# ATmega128RFA1-DevBoard-rev2_routed.net
KiCad netlist of a schematic drawn in EAGLE
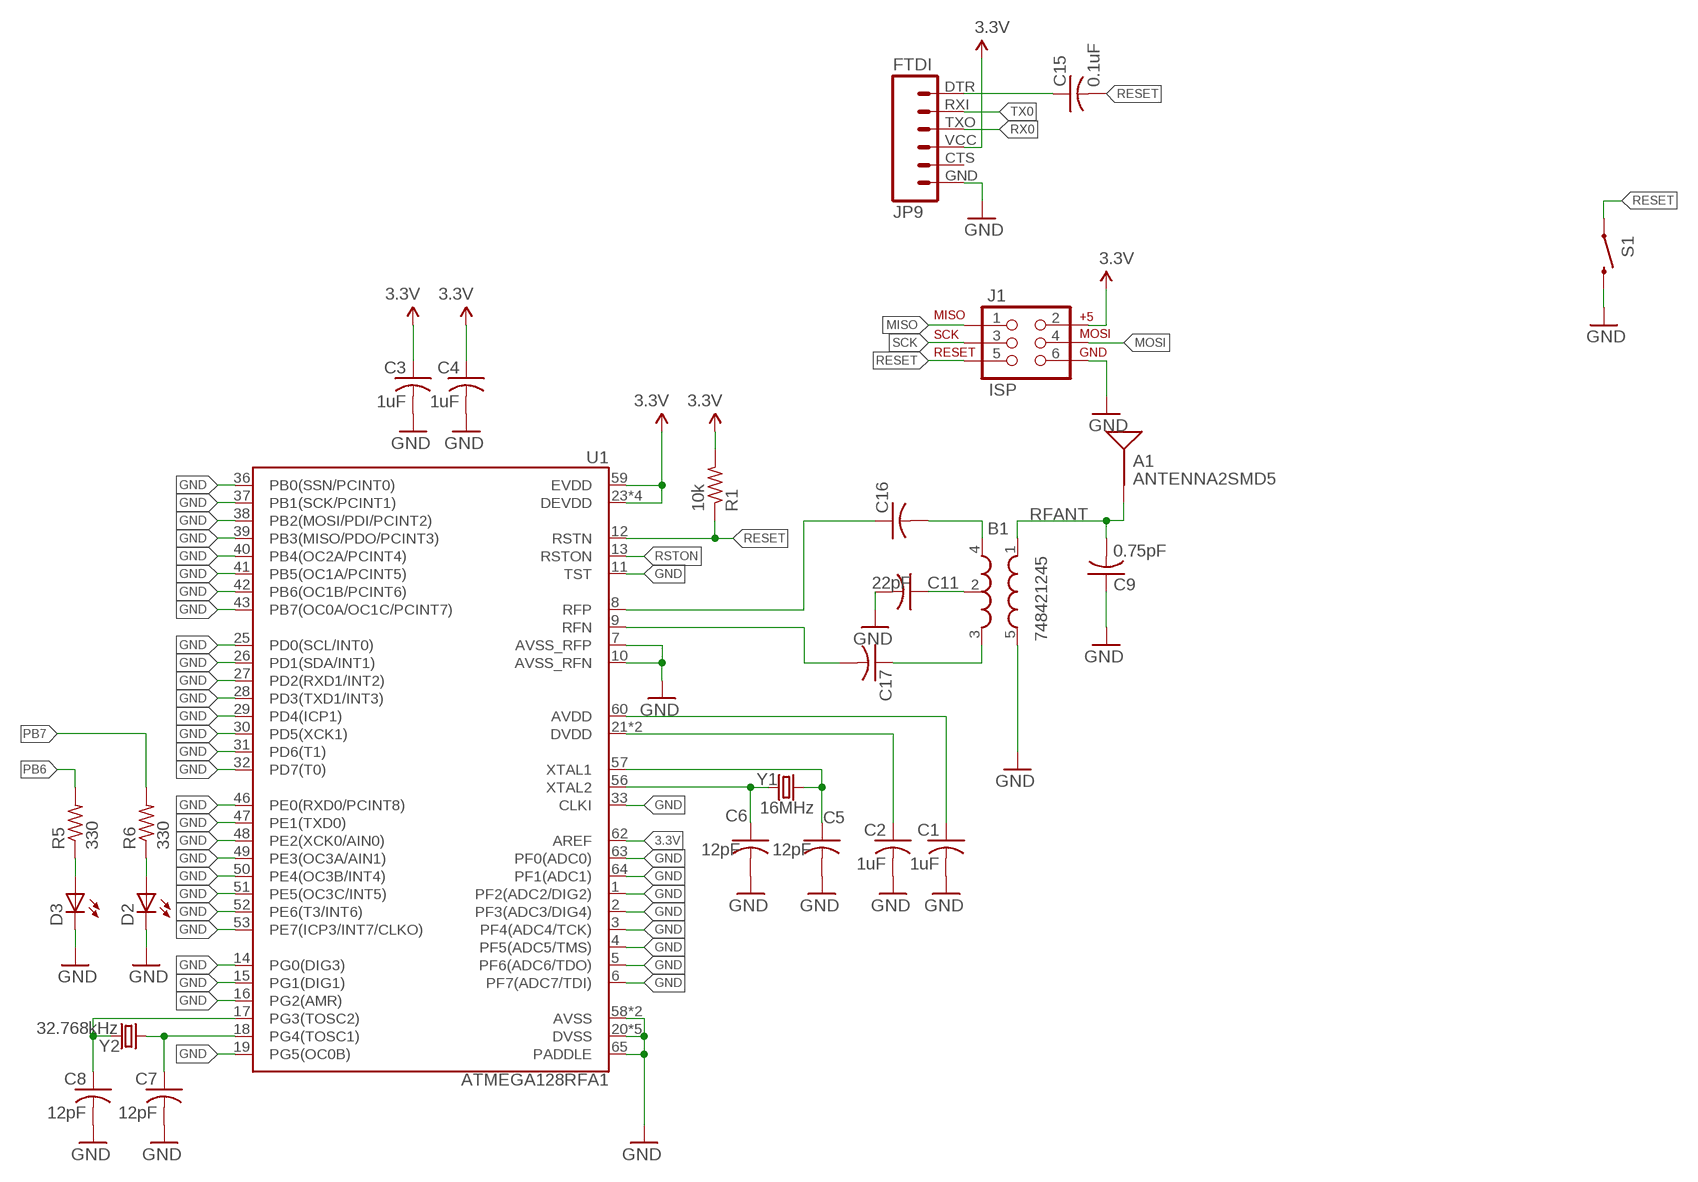
[diagram p0: schematic, sheet 1]

(export (version "E")
  (design (tool "Eeschema 10.0.6"))
  (components
    (comp (ref "A1")
      (value "ANTENNA2SMD5")
      (footprint "eagle-import:ANTENNA-CHIP5")
      (libsource (lib "eagle-import") (part "ANTENNA2SMD5"))
    )
    (comp (ref "B1")
      (value "748421245")
      (footprint "eagle-import:BALUN")
      (libsource (lib "eagle-import") (part "BALUN0805"))
    )
    (comp (ref "C1")
      (value "1uF")
      (footprint "eagle-import:C0805")
      (libsource (lib "eagle-import") (part "C-USC0805"))
    )
    (comp (ref "C2")
      (value "1uF")
      (footprint "eagle-import:C0805")
      (libsource (lib "eagle-import") (part "C-USC0805"))
    )
    (comp (ref "C3")
      (value "1uF")
      (footprint "eagle-import:C0805")
      (libsource (lib "eagle-import") (part "C-USC0805"))
    )
    (comp (ref "C4")
      (value "1uF")
      (footprint "eagle-import:C0805")
      (libsource (lib "eagle-import") (part "C-USC0805"))
    )
    (comp (ref "C5")
      (value "12pF")
      (footprint "eagle-import:C0805")
      (libsource (lib "eagle-import") (part "C-USC0805"))
    )
    (comp (ref "C6")
      (value "12pF")
      (footprint "eagle-import:C0805")
      (libsource (lib "eagle-import") (part "C-USC0805"))
    )
    (comp (ref "C7")
      (value "12pF")
      (footprint "eagle-import:C0805")
      (libsource (lib "eagle-import") (part "C-USC0805"))
    )
    (comp (ref "C8")
      (value "12pF")
      (footprint "eagle-import:C0805")
      (libsource (lib "eagle-import") (part "C-USC0805"))
    )
    (comp (ref "C9")
      (value "0.75pF")
      (footprint "eagle-import:C0805")
      (libsource (lib "eagle-import") (part "C-USC0805"))
    )
    (comp (ref "C11")
      (value "22pF")
      (footprint "eagle-import:C0805")
      (libsource (lib "eagle-import") (part "C-USC0805"))
    )
    (comp (ref "C15")
      (value "0.1uF")
      (footprint "eagle-import:C0805")
      (libsource (lib "eagle-import") (part "C-USC0805"))
    )
    (comp (ref "C16")
      (value "C-USC0805")
      (footprint "eagle-import:C0805")
      (libsource (lib "eagle-import") (part "C-USC0805"))
    )
    (comp (ref "C17")
      (value "C-USC0805")
      (footprint "eagle-import:C0805")
      (libsource (lib "eagle-import") (part "C-USC0805"))
    )
    (comp (ref "D2")
      (value "LED5MM")
      (footprint "eagle-import:LED5MM")
      (libsource (lib "eagle-import") (part "LED5MM"))
    )
    (comp (ref "D3")
      (value "LED5MM")
      (footprint "eagle-import:LED5MM")
      (libsource (lib "eagle-import") (part "LED5MM"))
    )
    (comp (ref "J1")
      (value "ISP")
      (footprint "eagle-import:2X3-NS")
      (libsource (lib "eagle-import") (part "AVR_SPI_PRG_6NS"))
    )
    (comp (ref "JP9")
      (value "FTDI")
      (footprint "eagle-import:FTDI_BASIC")
      (libsource (lib "eagle-import") (part "FTDI_BASICPTH"))
    )
    (comp (ref "R1")
      (value "10k")
      (footprint "eagle-import:R0805")
      (libsource (lib "eagle-import") (part "R-US_R0805"))
    )
    (comp (ref "R5")
      (value "330")
      (footprint "eagle-import:R0805")
      (libsource (lib "eagle-import") (part "R-US_R0805"))
    )
    (comp (ref "R6")
      (value "330")
      (footprint "eagle-import:R0805")
      (libsource (lib "eagle-import") (part "R-US_R0805"))
    )
    (comp (ref "S1")
      (value "SWITCH-MOMENTARY-2SMD")
      (footprint "eagle-import:TACTILE_SWITCH_SMD")
      (libsource (lib "eagle-import") (part "SWITCH-MOMENTARY-2SMD"))
    )
    (comp (ref "U1")
      (value "ATMEGA128RFA1")
      (footprint "eagle-import:QFN-64")
      (libsource (lib "eagle-import") (part "ATMEGA128RFA1"))
    )
    (comp (ref "Y1")
      (value "16MHz")
      (footprint "eagle-import:CRYSTAL-SMD-5X3")
      (libsource (lib "eagle-import") (part "CRYSTAL5X3"))
    )
    (comp (ref "Y2")
      (value "32.768kHz")
      (footprint "eagle-import:CRYSTAL-32KHZ-SMD")
      (libsource (lib "eagle-import") (part "CRYSTAL32-SMD"))
    )
  )
  (nets
    (net (code "1") (name "/RFANT") (class "Default")
      (node (ref "A1") (pin "FEED") (pinfunction "SIGNAL_FEED") (pintype "bidirectional"))
      (node (ref "B1") (pin "1") (pinfunction "IN_1") (pintype "bidirectional"))
      (node (ref "C9") (pin "2") (pinfunction "2_2") (pintype "passive"))
    )
    (net (code "2") (name "3.3V") (class "Default")
      (node (ref "C3") (pin "1") (pinfunction "1_1") (pintype "passive"))
      (node (ref "C4") (pin "1") (pinfunction "1_1") (pintype "passive"))
      (node (ref "J1") (pin "2") (pinfunction "2_2") (pintype "passive"))
      (node (ref "JP9") (pin "VCC") (pinfunction "4_VCC") (pintype "passive"))
      (node (ref "R1") (pin "2") (pinfunction "2_2") (pintype "passive"))
      (node (ref "U1") (pin "23") (pinfunction "DEVDD_23") (pintype "bidirectional"))
      (node (ref "U1") (pin "34") (pinfunction "DEVDD_34") (pintype "bidirectional"))
      (node (ref "U1") (pin "44") (pinfunction "DEVDD_44") (pintype "bidirectional"))
      (node (ref "U1") (pin "54") (pinfunction "DEVDD_54") (pintype "bidirectional"))
      (node (ref "U1") (pin "59") (pinfunction "EVDD_59") (pintype "bidirectional"))
      (node (ref "U1") (pin "62") (pinfunction "AREF_62") (pintype "bidirectional"))
    )
    (net (code "3") (name "GND") (class "Default")
      (node (ref "B1") (pin "5") (pinfunction "GND_5") (pintype "bidirectional"))
      (node (ref "C1") (pin "2") (pinfunction "2_2") (pintype "passive"))
      (node (ref "C11") (pin "2") (pinfunction "2_2") (pintype "passive"))
      (node (ref "C2") (pin "2") (pinfunction "2_2") (pintype "passive"))
      (node (ref "C3") (pin "2") (pinfunction "2_2") (pintype "passive"))
      (node (ref "C4") (pin "2") (pinfunction "2_2") (pintype "passive"))
      (node (ref "C5") (pin "2") (pinfunction "2_2") (pintype "passive"))
      (node (ref "C6") (pin "2") (pinfunction "2_2") (pintype "passive"))
      (node (ref "C7") (pin "2") (pinfunction "2_2") (pintype "passive"))
      (node (ref "C8") (pin "2") (pinfunction "2_2") (pintype "passive"))
      (node (ref "C9") (pin "1") (pinfunction "1_1") (pintype "passive"))
      (node (ref "D2") (pin "K") (pinfunction "C_K") (pintype "passive"))
      (node (ref "D3") (pin "K") (pinfunction "C_K") (pintype "passive"))
      (node (ref "J1") (pin "6") (pinfunction "6_6") (pintype "passive"))
      (node (ref "JP9") (pin "GND") (pinfunction "6_GND") (pintype "passive"))
      (node (ref "S1") (pin "3") (pinfunction "2_3") (pintype "passive"))
      (node (ref "U1") (pin "1") (pinfunction "PF2(ADC2/DIG2)_1") (pintype "bidirectional"))
      (node (ref "U1") (pin "10") (pinfunction "AVSS_RFN_10") (pintype "bidirectional"))
      (node (ref "U1") (pin "11") (pinfunction "TST_11") (pintype "bidirectional"))
      (node (ref "U1") (pin "14") (pinfunction "PG0(DIG3)_14") (pintype "bidirectional"))
      (node (ref "U1") (pin "15") (pinfunction "PG1(DIG1)_15") (pintype "bidirectional"))
      (node (ref "U1") (pin "16") (pinfunction "PG2(AMR)_16") (pintype "bidirectional"))
      (node (ref "U1") (pin "19") (pinfunction "PG5(OC0B)_19") (pintype "bidirectional"))
      (node (ref "U1") (pin "2") (pinfunction "PF3(ADC3/DIG4)_2") (pintype "bidirectional"))
      (node (ref "U1") (pin "20") (pinfunction "DVSS_20") (pintype "bidirectional"))
      (node (ref "U1") (pin "24") (pinfunction "DVSS_24") (pintype "bidirectional"))
      (node (ref "U1") (pin "25") (pinfunction "PD0(SCL/INT0)_25") (pintype "bidirectional"))
      (node (ref "U1") (pin "26") (pinfunction "PD1(SDA/INT1)_26") (pintype "bidirectional"))
      (node (ref "U1") (pin "27") (pinfunction "PD2(RXD1/INT2)_27") (pintype "bidirectional"))
      (node (ref "U1") (pin "28") (pinfunction "PD3(TXD1/INT3)_28") (pintype "bidirectional"))
      (node (ref "U1") (pin "29") (pinfunction "PD4(ICP1)_29") (pintype "bidirectional"))
      (node (ref "U1") (pin "3") (pinfunction "PF4(ADC4/TCK)_3") (pintype "bidirectional"))
      (node (ref "U1") (pin "30") (pinfunction "PD5(XCK1)_30") (pintype "bidirectional"))
      (node (ref "U1") (pin "31") (pinfunction "PD6(T1)_31") (pintype "bidirectional"))
      (node (ref "U1") (pin "32") (pinfunction "PD7(T0)_32") (pintype "bidirectional"))
      (node (ref "U1") (pin "33") (pinfunction "CLKI_33") (pintype "bidirectional"))
      (node (ref "U1") (pin "35") (pinfunction "DVSS_35") (pintype "bidirectional"))
      (node (ref "U1") (pin "36") (pinfunction "PB0(SSN/PCINT0)_36") (pintype "bidirectional"))
      (node (ref "U1") (pin "37") (pinfunction "PB1(SCK/PCINT1)_37") (pintype "bidirectional"))
      (node (ref "U1") (pin "38") (pinfunction "PB2(MOSI/PDI/PCINT2)_38") (pintype "bidirectional"))
      (node (ref "U1") (pin "39") (pinfunction "PB3(MISO/PDO/PCINT3)_39") (pintype "bidirectional"))
      (node (ref "U1") (pin "4") (pinfunction "PF5(ADC5/TMS)_4") (pintype "bidirectional"))
      (node (ref "U1") (pin "40") (pinfunction "PB4(OC2A/PCINT4)_40") (pintype "bidirectional"))
      (node (ref "U1") (pin "41") (pinfunction "PB5(OC1A/PCINT5)_41") (pintype "bidirectional"))
      (node (ref "U1") (pin "42") (pinfunction "PB6(OC1B/PCINT6)_42") (pintype "bidirectional"))
      (node (ref "U1") (pin "43") (pinfunction "PB7(OC0A/OC1C/PCINT7)_43") (pintype "bidirectional"))
      (node (ref "U1") (pin "45") (pinfunction "DVSS_45") (pintype "bidirectional"))
      (node (ref "U1") (pin "46") (pinfunction "PE0(RXD0/PCINT8)_46") (pintype "bidirectional"))
      (node (ref "U1") (pin "47") (pinfunction "PE1(TXD0)_47") (pintype "bidirectional"))
      (node (ref "U1") (pin "48") (pinfunction "PE2(XCK0/AIN0)_48") (pintype "bidirectional"))
      (node (ref "U1") (pin "49") (pinfunction "PE3(OC3A/AIN1)_49") (pintype "bidirectional"))
      (node (ref "U1") (pin "5") (pinfunction "PF6(ADC6/TDO)_5") (pintype "bidirectional"))
      (node (ref "U1") (pin "50") (pinfunction "PE4(OC3B/INT4)_50") (pintype "bidirectional"))
      (node (ref "U1") (pin "51") (pinfunction "PE5(OC3C/INT5)_51") (pintype "bidirectional"))
      (node (ref "U1") (pin "52") (pinfunction "PE6(T3/INT6)_52") (pintype "bidirectional"))
      (node (ref "U1") (pin "53") (pinfunction "PE7(ICP3/INT7/CLKO)_53") (pintype "bidirectional"))
      (node (ref "U1") (pin "55") (pinfunction "DVSS_55") (pintype "bidirectional"))
      (node (ref "U1") (pin "58") (pinfunction "AVSS_58") (pintype "bidirectional"))
      (node (ref "U1") (pin "6") (pinfunction "PF7(ADC7/TDI)_6") (pintype "bidirectional"))
      (node (ref "U1") (pin "61") (pinfunction "AVSS_61") (pintype "bidirectional"))
      (node (ref "U1") (pin "63") (pinfunction "PF0(ADC0)_63") (pintype "bidirectional"))
      (node (ref "U1") (pin "64") (pinfunction "PF1(ADC1)_64") (pintype "bidirectional"))
      (node (ref "U1") (pin "65") (pinfunction "PADDLE_65") (pintype "bidirectional"))
      (node (ref "U1") (pin "7") (pinfunction "AVSS_RFP_7") (pintype "bidirectional"))
    )
    (net (code "4") (name "MISO") (class "Default")
      (node (ref "J1") (pin "1") (pinfunction "1_1") (pintype "passive"))
    )
    (net (code "5") (name "MOSI") (class "Default")
      (node (ref "J1") (pin "4") (pinfunction "4_4") (pintype "passive"))
    )
    (net (code "6") (name "Net-(B1-GND-Pad2)") (class "Default")
      (node (ref "B1") (pin "2") (pinfunction "GND_2") (pintype "bidirectional"))
      (node (ref "C11") (pin "1") (pinfunction "1_1") (pintype "passive"))
    )
    (net (code "7") (name "Net-(B1-OUT1)") (class "Default")
      (node (ref "B1") (pin "4") (pinfunction "OUT1_4") (pintype "bidirectional"))
      (node (ref "C16") (pin "2") (pinfunction "2_2") (pintype "passive"))
    )
    (net (code "8") (name "Net-(B1-OUT2)") (class "Default")
      (node (ref "B1") (pin "3") (pinfunction "OUT2_3") (pintype "bidirectional"))
      (node (ref "C17") (pin "1") (pinfunction "1_1") (pintype "passive"))
    )
    (net (code "9") (name "Net-(C2-Pad1)") (class "Default")
      (node (ref "C2") (pin "1") (pinfunction "1_1") (pintype "passive"))
      (node (ref "U1") (pin "21") (pinfunction "DVDD_21") (pintype "bidirectional"))
      (node (ref "U1") (pin "22") (pinfunction "DVDD_22") (pintype "bidirectional"))
    )
    (net (code "10") (name "Net-(D2-PadA)") (class "Default")
      (node (ref "D2") (pin "A") (pinfunction "A_A") (pintype "passive"))
      (node (ref "R6") (pin "1") (pinfunction "1_1") (pintype "passive"))
    )
    (net (code "11") (name "Net-(D3-PadA)") (class "Default")
      (node (ref "D3") (pin "A") (pinfunction "A_A") (pintype "passive"))
      (node (ref "R5") (pin "1") (pinfunction "1_1") (pintype "passive"))
    )
    (net (code "12") (name "Net-(JP9-1)") (class "Default")
      (node (ref "C15") (pin "1") (pinfunction "1_1") (pintype "passive"))
      (node (ref "JP9") (pin "DTR") (pinfunction "1_DTR") (pintype "passive"))
    )
    (net (code "13") (name "Net-(U1-AVDD)") (class "Default")
      (node (ref "C1") (pin "1") (pinfunction "1_1") (pintype "passive"))
      (node (ref "U1") (pin "60") (pinfunction "AVDD_60") (pintype "bidirectional"))
    )
    (net (code "14") (name "Net-(U1-PG3(TOSC2))") (class "Default")
      (node (ref "C8") (pin "1") (pinfunction "1_1") (pintype "passive"))
      (node (ref "U1") (pin "17") (pinfunction "PG3(TOSC2)_17") (pintype "bidirectional"))
      (node (ref "Y2") (pin "X2") (pinfunction "2_X2") (pintype "passive"))
    )
    (net (code "15") (name "Net-(U1-PG4(TOSC1))") (class "Default")
      (node (ref "C7") (pin "1") (pinfunction "1_1") (pintype "passive"))
      (node (ref "U1") (pin "18") (pinfunction "PG4(TOSC1)_18") (pintype "bidirectional"))
      (node (ref "Y2") (pin "X1") (pinfunction "1_X1") (pintype "passive"))
    )
    (net (code "16") (name "Net-(U1-RFN)") (class "Default")
      (node (ref "C17") (pin "2") (pinfunction "2_2") (pintype "passive"))
      (node (ref "U1") (pin "9") (pinfunction "RFN_9") (pintype "bidirectional"))
    )
    (net (code "17") (name "Net-(U1-RFP)") (class "Default")
      (node (ref "C16") (pin "1") (pinfunction "1_1") (pintype "passive"))
      (node (ref "U1") (pin "8") (pinfunction "RFP_8") (pintype "bidirectional"))
    )
    (net (code "18") (name "Net-(U1-XTAL1)") (class "Default")
      (node (ref "C5") (pin "1") (pinfunction "1_1") (pintype "passive"))
      (node (ref "U1") (pin "57") (pinfunction "XTAL1_57") (pintype "bidirectional"))
      (node (ref "Y1") (pin "3") (pinfunction "2_3") (pintype "passive"))
    )
    (net (code "19") (name "Net-(U1-XTAL2)") (class "Default")
      (node (ref "C6") (pin "1") (pinfunction "1_1") (pintype "passive"))
      (node (ref "U1") (pin "56") (pinfunction "XTAL2_56") (pintype "bidirectional"))
      (node (ref "Y1") (pin "1") (pinfunction "1_1") (pintype "passive"))
    )
    (net (code "20") (name "PB6") (class "Default")
      (node (ref "R5") (pin "2") (pinfunction "2_2") (pintype "passive"))
    )
    (net (code "21") (name "PB7") (class "Default")
      (node (ref "R6") (pin "2") (pinfunction "2_2") (pintype "passive"))
    )
    (net (code "22") (name "RESET") (class "Default")
      (node (ref "C15") (pin "2") (pinfunction "2_2") (pintype "passive"))
      (node (ref "J1") (pin "5") (pinfunction "5_5") (pintype "passive"))
      (node (ref "R1") (pin "1") (pinfunction "1_1") (pintype "passive"))
      (node (ref "S1") (pin "1") (pinfunction "1_1") (pintype "passive"))
      (node (ref "U1") (pin "12") (pinfunction "RSTN_12") (pintype "bidirectional"))
    )
    (net (code "23") (name "RSTON") (class "Default")
      (node (ref "U1") (pin "13") (pinfunction "RSTON_13") (pintype "bidirectional"))
    )
    (net (code "24") (name "RX0") (class "Default")
      (node (ref "JP9") (pin "TXO") (pinfunction "3_TXO") (pintype "passive"))
    )
    (net (code "25") (name "SCK") (class "Default")
      (node (ref "J1") (pin "3") (pinfunction "3_3") (pintype "passive"))
    )
    (net (code "26") (name "TX0") (class "Default")
      (node (ref "JP9") (pin "RXI") (pinfunction "2_RXI") (pintype "passive"))
    )
    (net (code "27") (name "unconnected-(JP9-5-PadCTS)") (class "Default")
      (node (ref "JP9") (pin "CTS") (pinfunction "5_CTS") (pintype "passive"))
    )
  )
)
